# RANGE-FINDER-NODE-SCH.net
KiCad netlist of a schematic drawn in Altium Designer
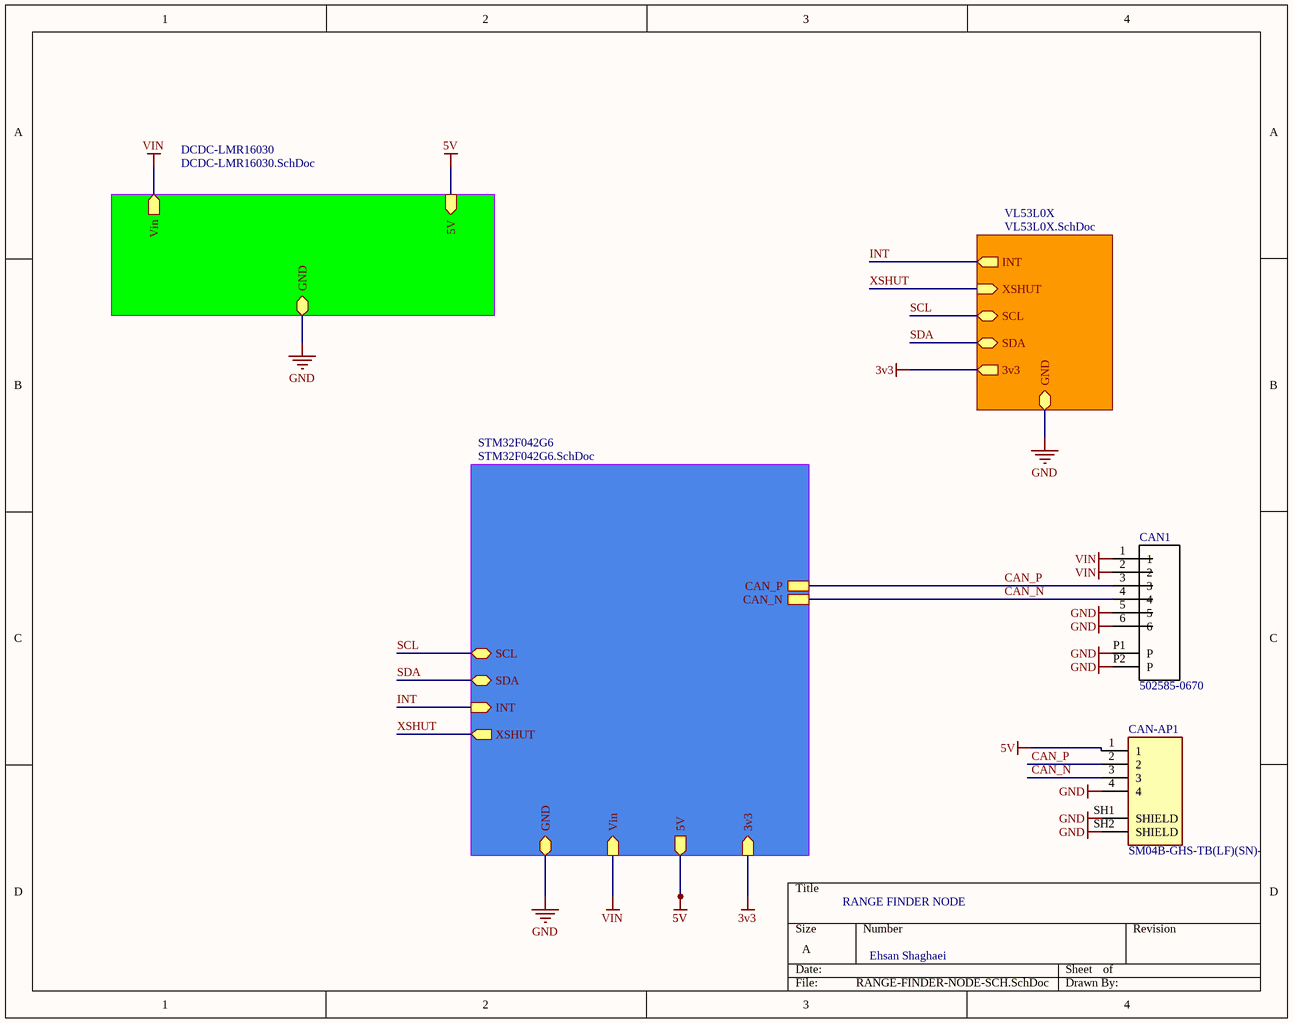
[diagram p0: RANGE-FINDER-NODE-SCH.SchDoc]

(export (version "E")
  (design (tool "Eeschema 10.0.6"))
  (components
    (comp (ref "CAN-AP1")
      (value "SM04B-GHS-TB(LF)(SN)-")
      (footprint "JST_SM04B-GHS-TB(LF)(SN)-")
      (description "Connector Header Surface Mount, Right Angle 4 position 0.049 _1.25mm_")
      (fields (field (name "MP") "SM04B-GHS-TB(LF)(SN)") (field (name "MF") "JST Sales"))
      (libsource (lib "lib") (part "SM04B-GHS-TB(LF)(SN)-"))
    )
    (comp (ref "CAN1")
      (value "502585-0670")
      (footprint "MOLEX_502585-0670")
      (fields (field (name "MF") "Molex"))
      (libsource (lib "lib") (part "502585-0670"))
    )
  )
  (nets
    (net (code "1") (name "/CAN_N") (class "Default")
      (node (ref "CAN-AP1") (pin "3") (pinfunction "3_3") (pintype "passive"))
      (node (ref "CAN1") (pin "4") (pinfunction "4_4") (pintype "passive"))
    )
    (net (code "2") (name "/CAN_P") (class "Default")
      (node (ref "CAN-AP1") (pin "2") (pinfunction "2_2") (pintype "passive"))
      (node (ref "CAN1") (pin "3") (pinfunction "3_3") (pintype "passive"))
    )
    (net (code "8") (name "5V") (class "Default")
      (node (ref "CAN-AP1") (pin "1") (pinfunction "1_1") (pintype "passive"))
    )
    (net (code "9") (name "GND") (class "Default")
      (node (ref "CAN-AP1") (pin "4") (pinfunction "4_4") (pintype "passive"))
      (node (ref "CAN-AP1") (pin "SH1") (pinfunction "SHIELD_SH1") (pintype "power_in"))
      (node (ref "CAN-AP1") (pin "SH2") (pinfunction "SHIELD_SH2") (pintype "power_in"))
      (node (ref "CAN1") (pin "5") (pinfunction "5_5") (pintype "passive"))
      (node (ref "CAN1") (pin "6") (pinfunction "6_6") (pintype "passive"))
      (node (ref "CAN1") (pin "P1") (pinfunction "P_P1") (pintype "passive"))
      (node (ref "CAN1") (pin "P2") (pinfunction "P_P2") (pintype "passive"))
    )
    (net (code "10") (name "VIN") (class "Default")
      (node (ref "CAN1") (pin "1") (pinfunction "1_1") (pintype "passive"))
      (node (ref "CAN1") (pin "2") (pinfunction "2_2") (pintype "passive"))
    )
  )
)
